# WeatherSharkCustom.net
KiCad netlist of a schematic drawn in EAGLE
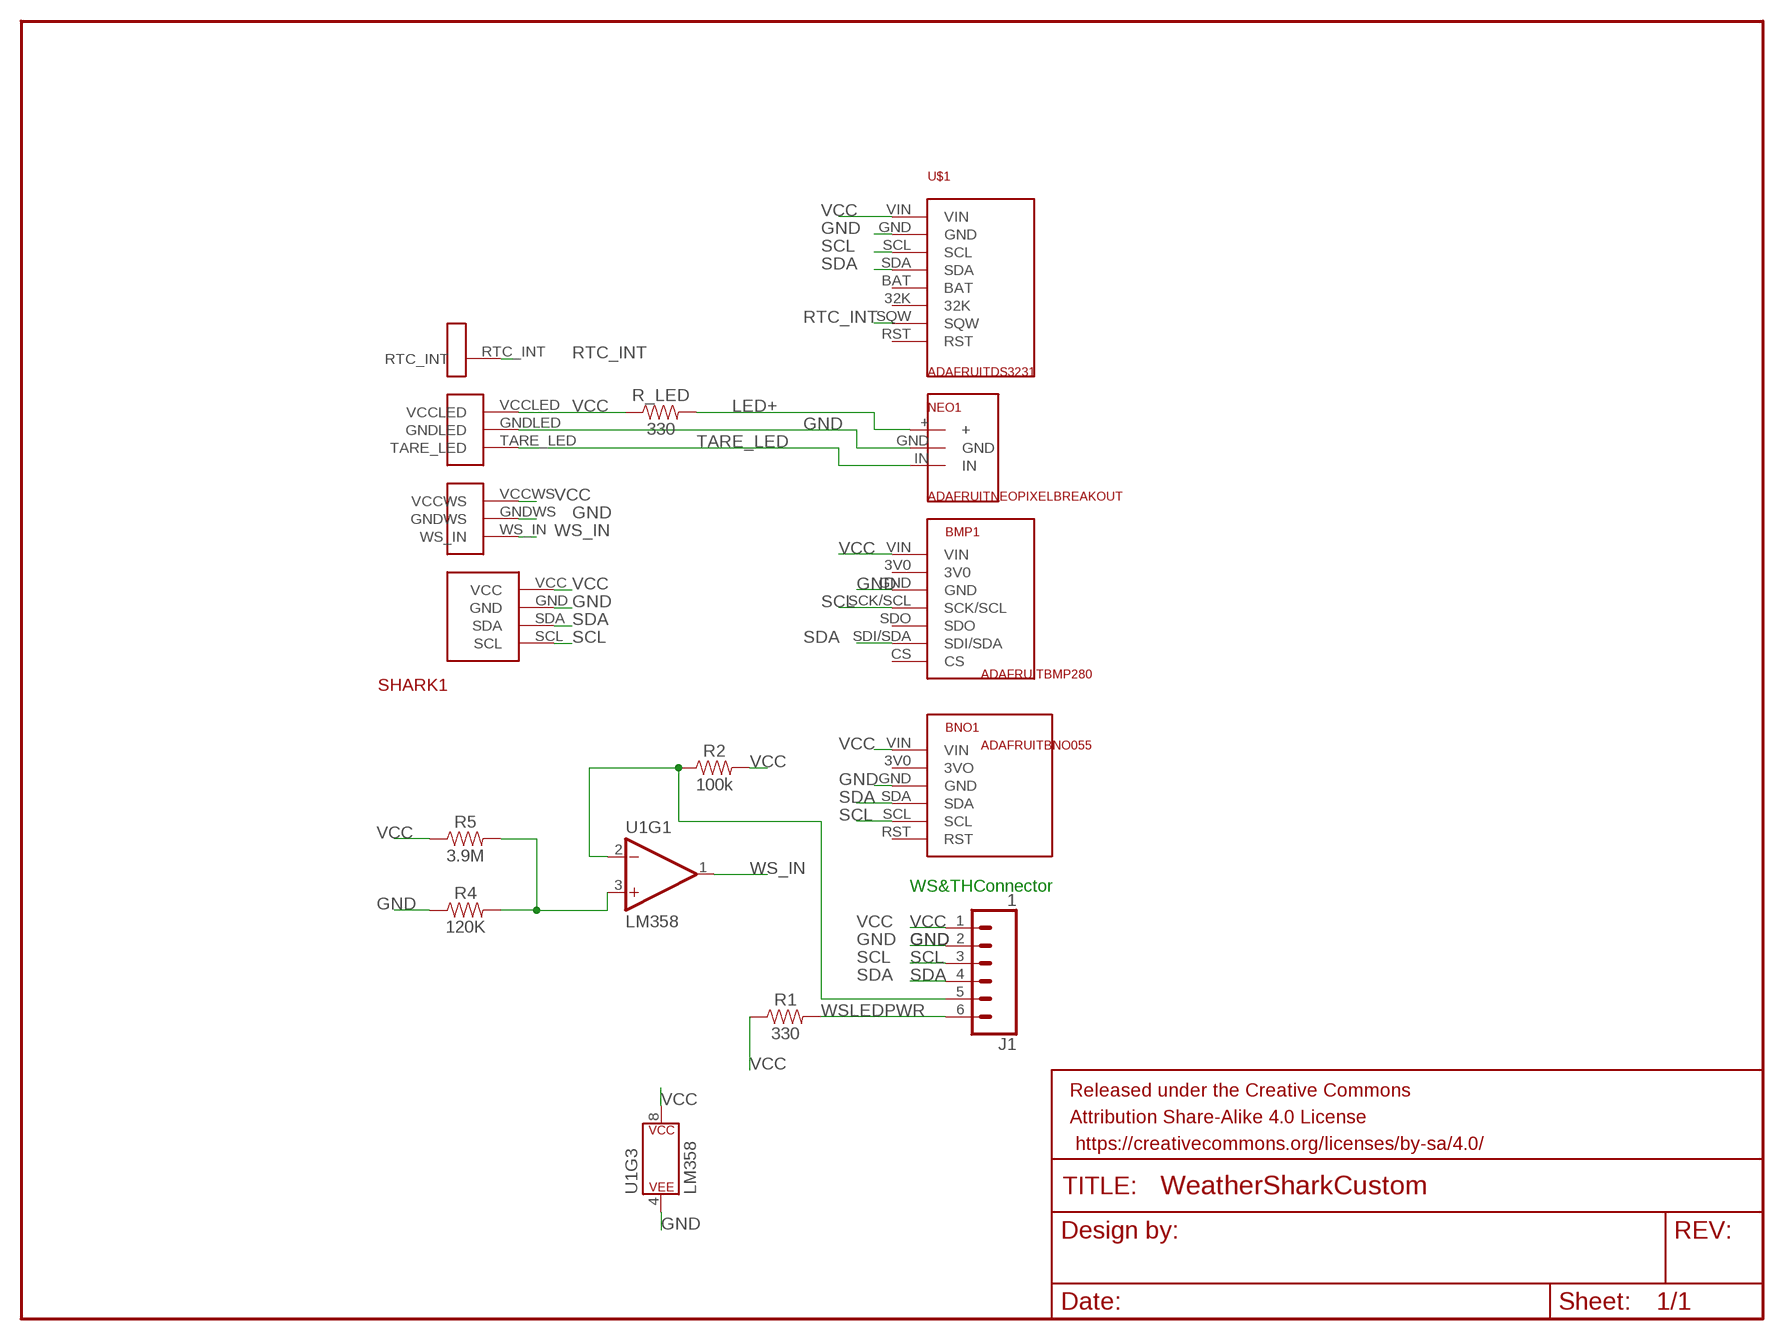
[diagram p0: schematic, sheet 1]

(export (version "E")
  (design (tool "Eeschema 10.0.6"))
  (components
    (comp (ref "BMP1")
      (value "ADAFRUITBMP280")
      (footprint "eagle-import:ADAFRUITBMP280")
      (libsource (lib "eagle-import") (part "ADAFRUITBMP280"))
    )
    (comp (ref "BNO1")
      (value "ADAFRUITBNO055")
      (footprint "eagle-import:ADAFRUITBNO055")
      (libsource (lib "eagle-import") (part "ADAFRUITBNO055"))
    )
    (comp (ref "FRAME1")
      (value "FRAME-LETTER")
      (footprint "eagle-import:CREATIVE_COMMONS")
      (libsource (lib "eagle-import") (part "FRAME-LETTER"))
    )
    (comp (ref "J1")
      (value "1")
      (footprint "eagle-import:MOLEX-1X6")
      (libsource (lib "eagle-import") (part "CONN_06POLAR"))
    )
    (comp (ref "NEO1")
      (value "ADAFRUITNEOPIXELBREAKOUT")
      (footprint "eagle-import:ADAFRUITNEOPIXELBREAKOUT")
      (libsource (lib "eagle-import") (part "ADAFRUITNEOPIXELBREAKOUT"))
    )
    (comp (ref "R1")
      (value "330")
      (footprint "eagle-import:AXIAL-0.3")
      (libsource (lib "eagle-import") (part "330OHM-HORIZ-1/10W-5%"))
    )
    (comp (ref "R2")
      (value "100k")
      (footprint "eagle-import:AXIAL-0.3")
      (libsource (lib "eagle-import") (part "100KOHM-HORIZ-1/4W-1%"))
    )
    (comp (ref "R4")
      (value "120K")
      (footprint "eagle-import:AXIAL-0.3")
      (libsource (lib "eagle-import") (part "330OHM-HORIZ-1/10W-5%"))
    )
    (comp (ref "R5")
      (value "3.9M")
      (footprint "eagle-import:AXIAL-0.3")
      (libsource (lib "eagle-import") (part "330OHM-HORIZ-1/10W-5%"))
    )
    (comp (ref "R_LED")
      (value "330")
      (footprint "eagle-import:AXIAL-0.3")
      (libsource (lib "eagle-import") (part "330OHM-HORIZ-1/10W-5%"))
    )
    (comp (ref "SHARK1")
      (value "EVAPSHARK")
      (footprint "eagle-import:EVAPSHARK")
      (libsource (lib "eagle-import") (part "EVAPSHARK"))
    )
    (comp (ref "U$1")
      (value "ADAFRUITDS3231")
      (footprint "eagle-import:ADAFRUITDS3231")
      (libsource (lib "eagle-import") (part "ADAFRUITDS3231"))
    )
    (comp (ref "U1")
      (value "LM358")
      (footprint "eagle-import:DIP08-KIT")
      (libsource (lib "eagle-import") (part "LM358KIT"))
    )
  )
  (nets
    (net (code "1") (name "/GND") (class "Default")
      (node (ref "BMP1") (pin "GND") (pinfunction "GND_GND") (pintype "power_in"))
      (node (ref "BNO1") (pin "GND") (pinfunction "GND_GND") (pintype "power_in"))
      (node (ref "J1") (pin "2") (pinfunction "2_2") (pintype "passive"))
      (node (ref "NEO1") (pin "GND") (pinfunction "GND_GND") (pintype "power_in"))
      (node (ref "R4") (pin "P$1") (pinfunction "1_P$1") (pintype "passive"))
      (node (ref "SHARK1") (pin "GND") (pinfunction "GND_GND") (pintype "power_in"))
      (node (ref "SHARK1") (pin "GNDLED") (pinfunction "GNDLED_GNDLED") (pintype "power_in"))
      (node (ref "SHARK1") (pin "GNDWS") (pinfunction "GNDWS_GNDWS") (pintype "power_in"))
      (node (ref "U$1") (pin "GND") (pinfunction "GND_GND") (pintype "power_in"))
      (node (ref "U1") (pin "4") (pinfunction "P$V-_4") (pintype "bidirectional"))
    )
    (net (code "2") (name "/LED+") (class "Default")
      (node (ref "NEO1") (pin "+") (pinfunction "+_+") (pintype "power_in"))
      (node (ref "R_LED") (pin "P$2") (pinfunction "2_P$2") (pintype "passive"))
    )
    (net (code "3") (name "/RTC_INT") (class "Default")
      (node (ref "SHARK1") (pin "RTC_INT") (pinfunction "RTC_INT_RTC_INT") (pintype "bidirectional"))
      (node (ref "U$1") (pin "SQW") (pinfunction "SQW_SQW") (pintype "bidirectional"))
    )
    (net (code "4") (name "/SCL") (class "Default")
      (node (ref "BMP1") (pin "SCK/SCL") (pinfunction "SCK/SCL_SCK/SCL") (pintype "bidirectional"))
      (node (ref "BNO1") (pin "SCL") (pinfunction "SCL_SCL") (pintype "bidirectional"))
      (node (ref "J1") (pin "3") (pinfunction "3_3") (pintype "passive"))
      (node (ref "SHARK1") (pin "SCL") (pinfunction "SCL_SCL") (pintype "bidirectional"))
      (node (ref "U$1") (pin "SCL") (pinfunction "SCL_SCL") (pintype "bidirectional"))
    )
    (net (code "5") (name "/SDA") (class "Default")
      (node (ref "BMP1") (pin "SDI/SDA") (pinfunction "SDI/SDA_SDI/SDA") (pintype "bidirectional"))
      (node (ref "BNO1") (pin "SDA") (pinfunction "SDA_SDA") (pintype "bidirectional"))
      (node (ref "J1") (pin "4") (pinfunction "4_4") (pintype "passive"))
      (node (ref "SHARK1") (pin "SDA") (pinfunction "SDA_SDA") (pintype "bidirectional"))
      (node (ref "U$1") (pin "SDA") (pinfunction "SDA_SDA") (pintype "bidirectional"))
    )
    (net (code "6") (name "/TARE_LED") (class "Default")
      (node (ref "NEO1") (pin "IN") (pinfunction "IN_IN") (pintype "bidirectional"))
      (node (ref "SHARK1") (pin "TARE_LED") (pinfunction "TARE_LED_TARE_LED") (pintype "bidirectional"))
    )
    (net (code "7") (name "/VCC") (class "Default")
      (node (ref "BMP1") (pin "VIN") (pinfunction "VIN_VIN") (pintype "power_in"))
      (node (ref "BNO1") (pin "VIN") (pinfunction "VIN_VIN") (pintype "power_in"))
      (node (ref "J1") (pin "1") (pinfunction "1_1") (pintype "passive"))
      (node (ref "R1") (pin "P$1") (pinfunction "1_P$1") (pintype "passive"))
      (node (ref "R2") (pin "P$2") (pinfunction "2_P$2") (pintype "passive"))
      (node (ref "R5") (pin "P$1") (pinfunction "1_P$1") (pintype "passive"))
      (node (ref "R_LED") (pin "P$1") (pinfunction "1_P$1") (pintype "passive"))
      (node (ref "SHARK1") (pin "VCC") (pinfunction "VCC_VCC") (pintype "power_in"))
      (node (ref "SHARK1") (pin "VCCLED") (pinfunction "VCCLED_VCCLED") (pintype "power_in"))
      (node (ref "SHARK1") (pin "VCCWS") (pinfunction "VCCWS_VCCWS") (pintype "power_in"))
      (node (ref "U$1") (pin "VIN") (pinfunction "VIN_VIN") (pintype "power_in"))
      (node (ref "U1") (pin "8") (pinfunction "P$V+_8") (pintype "bidirectional"))
    )
    (net (code "8") (name "/WSLEDPWR") (class "Default")
      (node (ref "J1") (pin "6") (pinfunction "6_6") (pintype "passive"))
      (node (ref "R1") (pin "P$2") (pinfunction "2_P$2") (pintype "passive"))
    )
    (net (code "9") (name "/WS_IN") (class "Default")
      (node (ref "SHARK1") (pin "WS_IN") (pinfunction "WS_IN_WS_IN") (pintype "bidirectional"))
      (node (ref "U1") (pin "1") (pinfunction "OUT_1") (pintype "output"))
    )
    (net (code "10") (name "Net-(R2-1)") (class "Default")
      (node (ref "J1") (pin "5") (pinfunction "5_5") (pintype "passive"))
      (node (ref "R2") (pin "P$1") (pinfunction "1_P$1") (pintype "passive"))
      (node (ref "U1") (pin "2") (pinfunction "-IN_2") (pintype "input"))
    )
    (net (code "11") (name "Net-(R4-2)") (class "Default")
      (node (ref "R4") (pin "P$2") (pinfunction "2_P$2") (pintype "passive"))
      (node (ref "R5") (pin "P$2") (pinfunction "2_P$2") (pintype "passive"))
      (node (ref "U1") (pin "3") (pinfunction "+IN_3") (pintype "input"))
    )
    (net (code "12") (name "unconnected-(BMP1-Pad3V0)") (class "Default")
      (node (ref "BMP1") (pin "3V0") (pinfunction "3V0_3V0") (pintype "no_connect"))
    )
    (net (code "13") (name "unconnected-(BMP1-PadCS)") (class "Default")
      (node (ref "BMP1") (pin "CS") (pinfunction "CS_CS") (pintype "no_connect"))
    )
    (net (code "14") (name "unconnected-(BMP1-PadSDO)") (class "Default")
      (node (ref "BMP1") (pin "SDO") (pinfunction "SDO_SDO") (pintype "no_connect"))
    )
    (net (code "15") (name "unconnected-(BNO1-3VO-Pad3V0)") (class "Default")
      (node (ref "BNO1") (pin "3V0") (pinfunction "3VO_3V0") (pintype "no_connect"))
    )
    (net (code "16") (name "unconnected-(BNO1-PadRST)") (class "Default")
      (node (ref "BNO1") (pin "RST") (pinfunction "RST_RST") (pintype "no_connect"))
    )
    (net (code "17") (name "unconnected-(U$1-Pad32K)") (class "Default")
      (node (ref "U$1") (pin "32K") (pinfunction "32K_32K") (pintype "no_connect"))
    )
    (net (code "18") (name "unconnected-(U$1-PadBAT)") (class "Default")
      (node (ref "U$1") (pin "BAT") (pinfunction "BAT_BAT") (pintype "no_connect"))
    )
    (net (code "19") (name "unconnected-(U$1-PadRST)") (class "Default")
      (node (ref "U$1") (pin "RST") (pinfunction "RST_RST") (pintype "no_connect"))
    )
  )
)
